# OC_PROT.net
KiCad netlist of a schematic drawn in Altium Designer
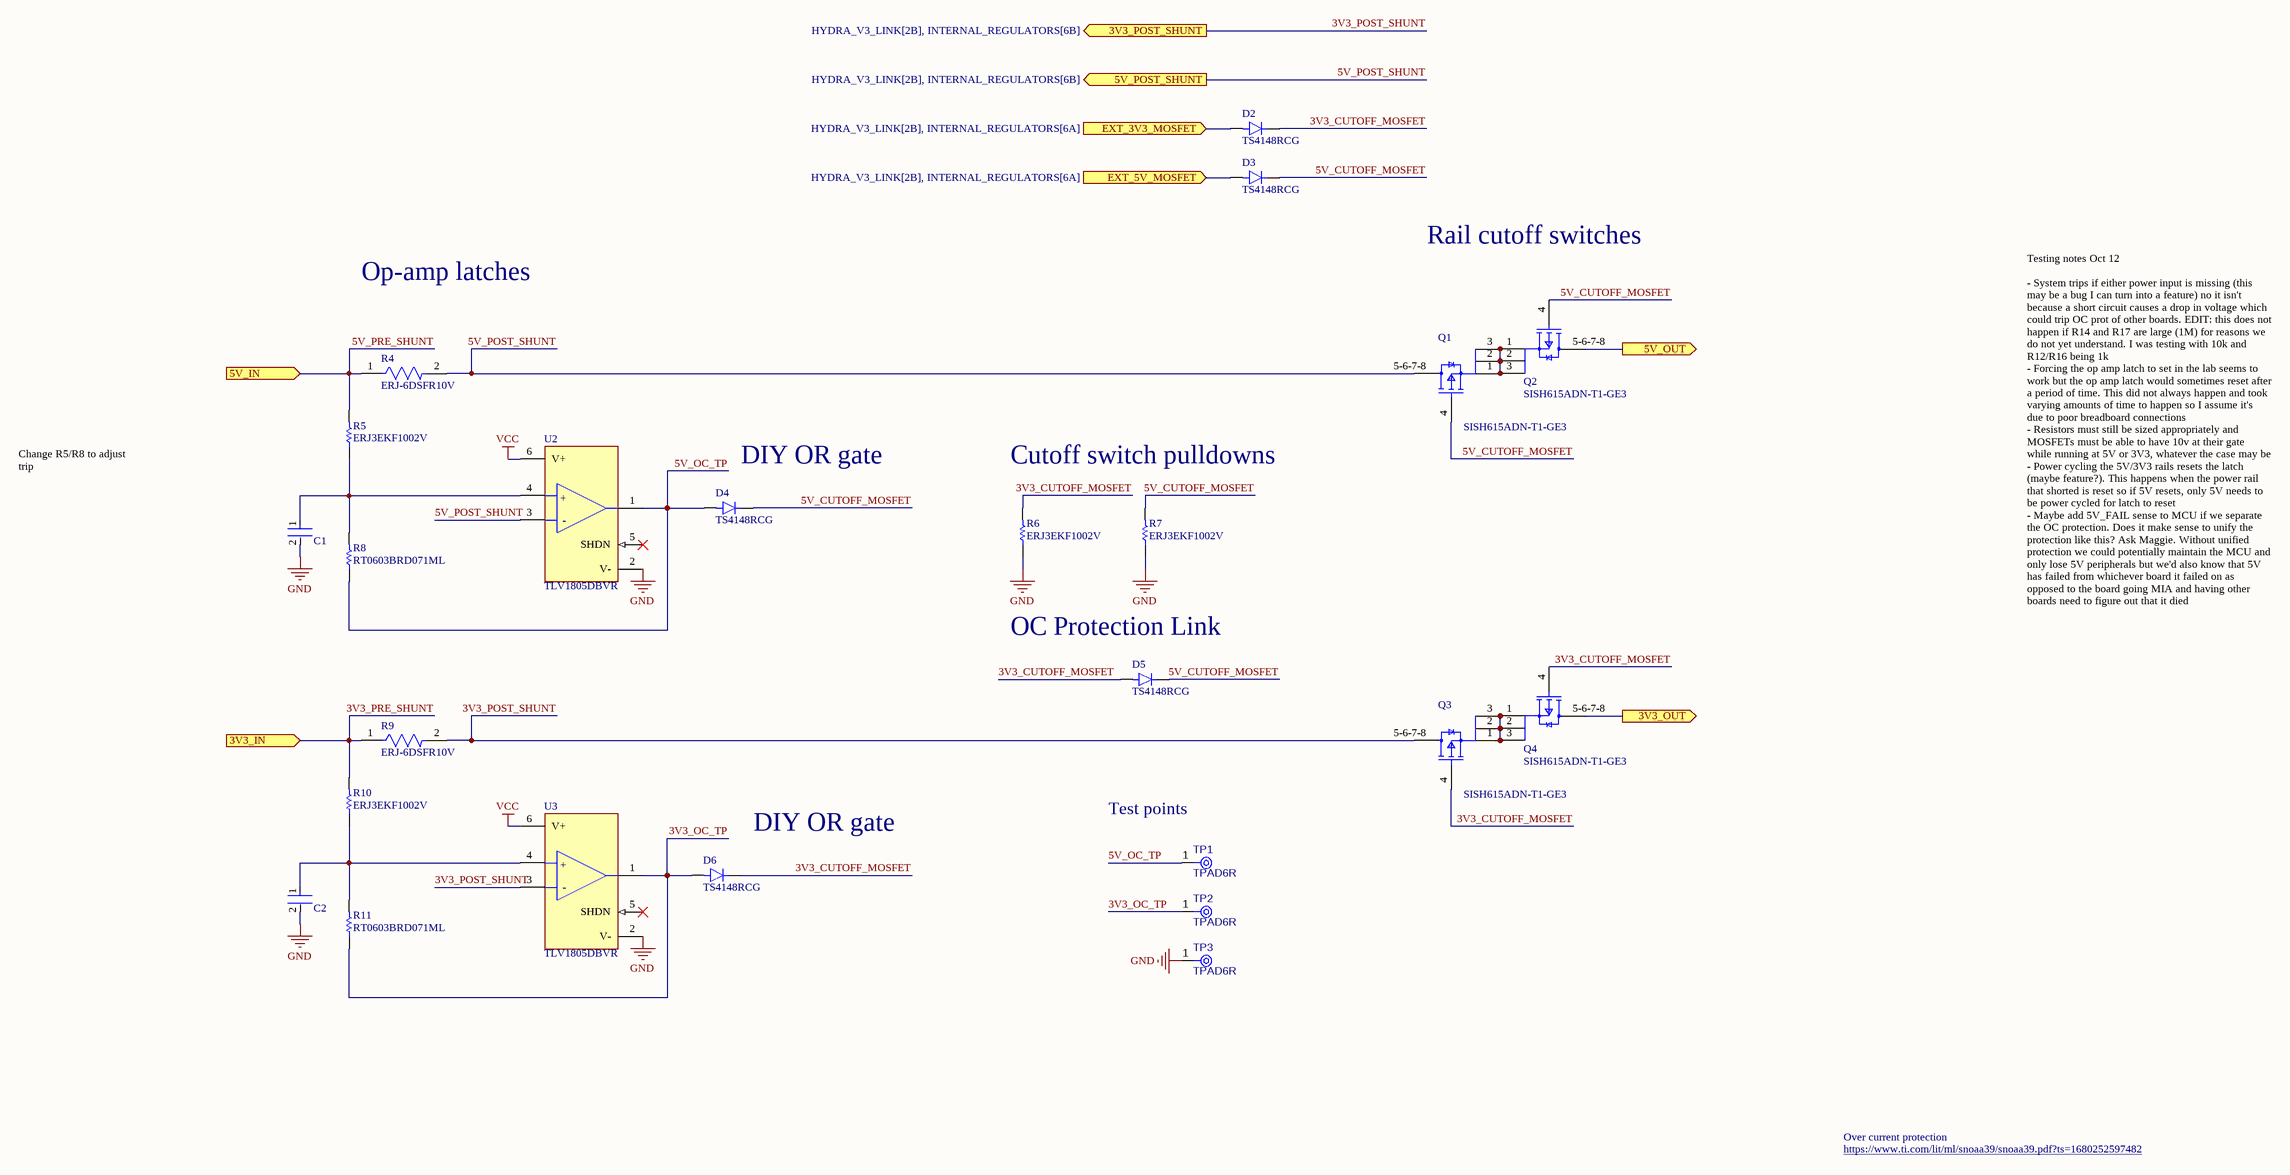
[diagram p0: OC_PROT.SchDoc]

(export (version "E")
  (design (tool "Eeschema 10.0.6"))
  (components
    (comp (ref "C1")
      (value "C0402C104K8PACTU")
      (footprint "FP-C0402-BB-MFG")
      (description "CAP CER 0.1UF 10V X5R 0402")
      (fields (field (name "MANUFACTURER") "Kemet") (field (name "TOLERANCE") "0.1"))
      (libsource (lib "Altium Content Vault") (part "b4654b650e69147ec39a6b967a45e02"))
    )
    (comp (ref "C2")
      (value "C0402C104K8PACTU")
      (footprint "FP-C0402-BB-MFG")
      (description "CAP CER 0.1UF 10V X5R 0402")
      (fields (field (name "MANUFACTURER") "Kemet") (field (name "TOLERANCE") "0.1"))
      (libsource (lib "Altium Content Vault") (part "b4654b650e69147ec39a6b967a45e02"))
    )
    (comp (ref "D2")
      (value "TS4148RCG")
      (footprint "TS4148RCG-Footprint-1")
      (description "SMD Si-Diode 75V 100mA 0603")
      (libsource (lib "uORocketry Hardware") (part "TS4148RCG"))
    )
    (comp (ref "D3")
      (value "TS4148RCG")
      (footprint "TS4148RCG-Footprint-1")
      (description "SMD Si-Diode 75V 100mA 0603")
      (libsource (lib "uORocketry Hardware") (part "TS4148RCG"))
    )
    (comp (ref "D4")
      (value "TS4148RCG")
      (footprint "TS4148RCG-Footprint-1")
      (description "SMD Si-Diode 75V 100mA 0603")
      (libsource (lib "uORocketry Hardware") (part "TS4148RCG"))
    )
    (comp (ref "D5")
      (value "TS4148RCG")
      (footprint "TS4148RCG-Footprint-1")
      (description "SMD Si-Diode 75V 100mA 0603")
      (libsource (lib "uORocketry Hardware") (part "TS4148RCG"))
    )
    (comp (ref "D6")
      (value "TS4148RCG")
      (footprint "TS4148RCG-Footprint-1")
      (description "SMD Si-Diode 75V 100mA 0603")
      (libsource (lib "uORocketry Hardware") (part "TS4148RCG"))
    )
    (comp (ref "Q1")
      (value "SISH615ADN-T1-GE3")
      (footprint "SISH615ADN-T1-GE3-Footprint-1")
      (description "Trans MOSFET P-CH 20V 22.1A 8-Pin PowerPAK 1212 EP T/R")
      (libsource (lib "uORocketry Hardware") (part "SISH615ADN-T1-GE3-Symbol-1"))
    )
    (comp (ref "Q2")
      (value "SISH615ADN-T1-GE3")
      (footprint "SISH615ADN-T1-GE3-Footprint-1")
      (description "Trans MOSFET P-CH 20V 22.1A 8-Pin PowerPAK 1212 EP T/R")
      (libsource (lib "uORocketry Hardware") (part "SISH615ADN-T1-GE3-Symbol-1"))
    )
    (comp (ref "Q3")
      (value "SISH615ADN-T1-GE3")
      (footprint "SISH615ADN-T1-GE3-Footprint-1")
      (description "Trans MOSFET P-CH 20V 22.1A 8-Pin PowerPAK 1212 EP T/R")
      (libsource (lib "uORocketry Hardware") (part "SISH615ADN-T1-GE3-Symbol-1"))
    )
    (comp (ref "Q4")
      (value "SISH615ADN-T1-GE3")
      (footprint "SISH615ADN-T1-GE3-Footprint-1")
      (description "Trans MOSFET P-CH 20V 22.1A 8-Pin PowerPAK 1212 EP T/R")
      (libsource (lib "uORocketry Hardware") (part "SISH615ADN-T1-GE3-Symbol-1"))
    )
    (comp (ref "R4")
      (value "ERJ-6DSFR10V")
      (footprint "FP-ERJ6D-MFG")
      (description "RES 0.1 OHM 1% 1/2W 0805")
      (fields (field (name "TOLERANCE") "1%"))
      (libsource (lib "Altium Content Vault") (part "1029c3af85768c4190bb7ad29bc67b5"))
    )
    (comp (ref "R5")
      (value "ERJ3EKF1002V")
      (footprint "RESC1609X55X30LL15T15")
      (description "Chip Resistor, 10 KOhm, +/- 1%, 0.1 W, -55 to 155 degC, 0603 (1608 Metric), RoHS, Tape and Reel")
      (fields (field (name "TOLERANCE") "1%") (field (name "MANUFACTURER") "Panasonic"))
      (libsource (lib "Altium Content Vault") (part "RES-2"))
    )
    (comp (ref "R6")
      (value "ERJ3EKF1002V")
      (footprint "RESC1609X55X30LL15T15")
      (description "Chip Resistor, 10 KOhm, +/- 1%, 0.1 W, -55 to 155 degC, 0603 (1608 Metric), RoHS, Tape and Reel")
      (fields (field (name "TOLERANCE") "1%") (field (name "MANUFACTURER") "Panasonic"))
      (libsource (lib "Altium Content Vault") (part "RES-2"))
    )
    (comp (ref "R7")
      (value "ERJ3EKF1002V")
      (footprint "RESC1609X55X30LL15T15")
      (description "Chip Resistor, 10 KOhm, +/- 1%, 0.1 W, -55 to 155 degC, 0603 (1608 Metric), RoHS, Tape and Reel")
      (fields (field (name "TOLERANCE") "1%") (field (name "MANUFACTURER") "Panasonic"))
      (libsource (lib "Altium Content Vault") (part "RES-2"))
    )
    (comp (ref "R8")
      (value "RT0603BRD071ML")
      (footprint "RESC1608X55X30NL20T20")
      (fields (field (name "MANUFACTURER") "Panasonic") (field (name "PART NUMBER") "ERA-3AEB163V"))
      (libsource (lib "Altium Content Vault") (part "RES"))
    )
    (comp (ref "R9")
      (value "ERJ-6DSFR10V")
      (footprint "FP-ERJ6D-MFG")
      (description "RES 0.1 OHM 1% 1/2W 0805")
      (fields (field (name "TOLERANCE") "1%"))
      (libsource (lib "Altium Content Vault") (part "1029c3af85768c4190bb7ad29bc67b5"))
    )
    (comp (ref "R10")
      (value "ERJ3EKF1002V")
      (footprint "RESC1609X55X30LL15T15")
      (description "Chip Resistor, 10 KOhm, +/- 1%, 0.1 W, -55 to 155 degC, 0603 (1608 Metric), RoHS, Tape and Reel")
      (fields (field (name "TOLERANCE") "1%") (field (name "MANUFACTURER") "Panasonic"))
      (libsource (lib "Altium Content Vault") (part "RES-2"))
    )
    (comp (ref "R11")
      (value "RT0603BRD071ML")
      (footprint "RESC1608X55X30NL20T20")
      (fields (field (name "MANUFACTURER") "Panasonic") (field (name "PART NUMBER") "ERA-3AEB163V"))
      (libsource (lib "Altium Content Vault") (part "RES"))
    )
    (comp (ref "TP1")
      (value "TPAD6R")
      (footprint "TP06R")
      (description "0.6mm round")
      (libsource (lib "uORocketry Hardware") (part "CMP-001-0001-4"))
    )
    (comp (ref "TP2")
      (value "TPAD6R")
      (footprint "TP06R")
      (description "0.6mm round")
      (libsource (lib "uORocketry Hardware") (part "CMP-001-0001-4"))
    )
    (comp (ref "TP3")
      (value "TPAD6R")
      (footprint "TP06R")
      (description "0.6mm round")
      (libsource (lib "uORocketry Hardware") (part "CMP-001-0001-4"))
    )
    (comp (ref "U2")
      (value "TLV1805DBVR")
      (footprint "FP-DBV0006A-IPC_C")
      (description "40V, RAIL-TO-RAIL INPUT, PUSH-PU")
      (libsource (lib "Altium Content Vault") (part "c7aa3bc3dbf0dc8b0b0354779bd1228"))
    )
    (comp (ref "U3")
      (value "TLV1805DBVR")
      (footprint "FP-DBV0006A-IPC_C")
      (description "40V, RAIL-TO-RAIL INPUT, PUSH-PU")
      (libsource (lib "Altium Content Vault") (part "c7aa3bc3dbf0dc8b0b0354779bd1228"))
    )
  )
  (nets
    (net (code "1") (name "/3V3_CUTOFF_MOSFET") (class "Default")
      (node (ref "D2") (pin "C") (pinfunction "K_C") (pintype "passive"))
      (node (ref "D5") (pin "A") (pinfunction "A_A") (pintype "passive"))
      (node (ref "D6") (pin "C") (pinfunction "K_C") (pintype "passive"))
      (node (ref "Q3") (pin "4") (pinfunction "G_4") (pintype "passive"))
      (node (ref "Q4") (pin "4") (pinfunction "G_4") (pintype "passive"))
      (node (ref "R6") (pin "2") (pinfunction "2_2") (pintype "passive"))
    )
    (net (code "2") (name "/3V3_OC_TP") (class "Default")
      (node (ref "D6") (pin "A") (pinfunction "A_A") (pintype "passive"))
      (node (ref "R11") (pin "1") (pinfunction "1_1") (pintype "passive"))
      (node (ref "TP2") (pin "1") (pinfunction "TP_1") (pintype "passive"))
      (node (ref "U3") (pin "1") (pinfunction "OUT_1") (pintype "passive"))
    )
    (net (code "3") (name "/3V3_OUT") (class "Default")
      (node (ref "Q4") (pin "5-6-7-8") (pinfunction "D_5-6-7-8") (pintype "passive"))
    )
    (net (code "4") (name "/3V3_POST_SHUNT") (class "Default")
      (node (ref "Q3") (pin "5-6-7-8") (pinfunction "D_5-6-7-8") (pintype "passive"))
      (node (ref "R9") (pin "2") (pinfunction "2_2") (pintype "passive"))
      (node (ref "U3") (pin "3") (pinfunction "-IN_3") (pintype "tri_state"))
    )
    (net (code "5") (name "/3V3_PRE_SHUNT") (class "Default")
      (node (ref "R10") (pin "2") (pinfunction "2_2") (pintype "passive"))
      (node (ref "R9") (pin "1") (pinfunction "1_1") (pintype "passive"))
    )
    (net (code "6") (name "/5V_CUTOFF_MOSFET") (class "Default")
      (node (ref "D3") (pin "C") (pinfunction "K_C") (pintype "passive"))
      (node (ref "D4") (pin "C") (pinfunction "K_C") (pintype "passive"))
      (node (ref "D5") (pin "C") (pinfunction "K_C") (pintype "passive"))
      (node (ref "Q1") (pin "4") (pinfunction "G_4") (pintype "passive"))
      (node (ref "Q2") (pin "4") (pinfunction "G_4") (pintype "passive"))
      (node (ref "R7") (pin "2") (pinfunction "2_2") (pintype "passive"))
    )
    (net (code "7") (name "/5V_OC_TP") (class "Default")
      (node (ref "D4") (pin "A") (pinfunction "A_A") (pintype "passive"))
      (node (ref "R8") (pin "1") (pinfunction "1_1") (pintype "passive"))
      (node (ref "TP1") (pin "1") (pinfunction "TP_1") (pintype "passive"))
      (node (ref "U2") (pin "1") (pinfunction "OUT_1") (pintype "passive"))
    )
    (net (code "8") (name "/5V_OUT") (class "Default")
      (node (ref "Q2") (pin "5-6-7-8") (pinfunction "D_5-6-7-8") (pintype "passive"))
    )
    (net (code "9") (name "/5V_POST_SHUNT") (class "Default")
      (node (ref "Q1") (pin "5-6-7-8") (pinfunction "D_5-6-7-8") (pintype "passive"))
      (node (ref "R4") (pin "2") (pinfunction "2_2") (pintype "passive"))
      (node (ref "U2") (pin "3") (pinfunction "-IN_3") (pintype "tri_state"))
    )
    (net (code "10") (name "/5V_PRE_SHUNT") (class "Default")
      (node (ref "R4") (pin "1") (pinfunction "1_1") (pintype "passive"))
      (node (ref "R5") (pin "2") (pinfunction "2_2") (pintype "passive"))
    )
    (net (code "11") (name "/EXT_3V3_MOSFET") (class "Default")
      (node (ref "D2") (pin "A") (pinfunction "A_A") (pintype "passive"))
    )
    (net (code "12") (name "/EXT_5V_MOSFET") (class "Default")
      (node (ref "D3") (pin "A") (pinfunction "A_A") (pintype "passive"))
    )
    (net (code "13") (name "GND") (class "Default")
      (node (ref "C1") (pin "2") (pinfunction "2_2") (pintype "passive"))
      (node (ref "C2") (pin "2") (pinfunction "2_2") (pintype "passive"))
      (node (ref "R6") (pin "1") (pinfunction "1_1") (pintype "passive"))
      (node (ref "R7") (pin "1") (pinfunction "1_1") (pintype "passive"))
      (node (ref "TP3") (pin "1") (pinfunction "TP_1") (pintype "passive"))
      (node (ref "U2") (pin "2") (pinfunction "V-_2") (pintype "power_in"))
      (node (ref "U3") (pin "2") (pinfunction "V-_2") (pintype "power_in"))
    )
    (net (code "14") (name "Net-(Q1-S-Pad1)") (class "Default")
      (node (ref "Q1") (pin "1") (pinfunction "S_1") (pintype "passive"))
      (node (ref "Q1") (pin "2") (pinfunction "S_2") (pintype "passive"))
      (node (ref "Q1") (pin "3") (pinfunction "S_3") (pintype "passive"))
      (node (ref "Q2") (pin "1") (pinfunction "S_1") (pintype "passive"))
      (node (ref "Q2") (pin "2") (pinfunction "S_2") (pintype "passive"))
      (node (ref "Q2") (pin "3") (pinfunction "S_3") (pintype "passive"))
    )
    (net (code "15") (name "Net-(Q3-S-Pad1)") (class "Default")
      (node (ref "Q3") (pin "1") (pinfunction "S_1") (pintype "passive"))
      (node (ref "Q3") (pin "2") (pinfunction "S_2") (pintype "passive"))
      (node (ref "Q3") (pin "3") (pinfunction "S_3") (pintype "passive"))
      (node (ref "Q4") (pin "1") (pinfunction "S_1") (pintype "passive"))
      (node (ref "Q4") (pin "2") (pinfunction "S_2") (pintype "passive"))
      (node (ref "Q4") (pin "3") (pinfunction "S_3") (pintype "passive"))
    )
    (net (code "16") (name "Net-(U2-+IN)") (class "Default")
      (node (ref "C1") (pin "1") (pinfunction "1_1") (pintype "passive"))
      (node (ref "R5") (pin "1") (pinfunction "1_1") (pintype "passive"))
      (node (ref "R8") (pin "2") (pinfunction "2_2") (pintype "passive"))
      (node (ref "U2") (pin "4") (pinfunction "+IN_4") (pintype "tri_state"))
    )
    (net (code "17") (name "Net-(U3-+IN)") (class "Default")
      (node (ref "C2") (pin "1") (pinfunction "1_1") (pintype "passive"))
      (node (ref "R10") (pin "1") (pinfunction "1_1") (pintype "passive"))
      (node (ref "R11") (pin "2") (pinfunction "2_2") (pintype "passive"))
      (node (ref "U3") (pin "4") (pinfunction "+IN_4") (pintype "tri_state"))
    )
    (net (code "18") (name "VCC") (class "Default")
      (node (ref "U2") (pin "6") (pinfunction "V+_6") (pintype "power_in"))
      (node (ref "U3") (pin "6") (pinfunction "V+_6") (pintype "power_in"))
    )
    (net (code "19") (name "unconnected-(U2-SHDN-Pad5)") (class "Default")
      (node (ref "U2") (pin "5") (pinfunction "SHDN_5") (pintype "input+no_connect"))
    )
    (net (code "20") (name "unconnected-(U3-SHDN-Pad5)") (class "Default")
      (node (ref "U3") (pin "5") (pinfunction "SHDN_5") (pintype "input+no_connect"))
    )
  )
)
